# HPA_Module_V1p1.net
KiCad netlist of a schematic drawn in EAGLE
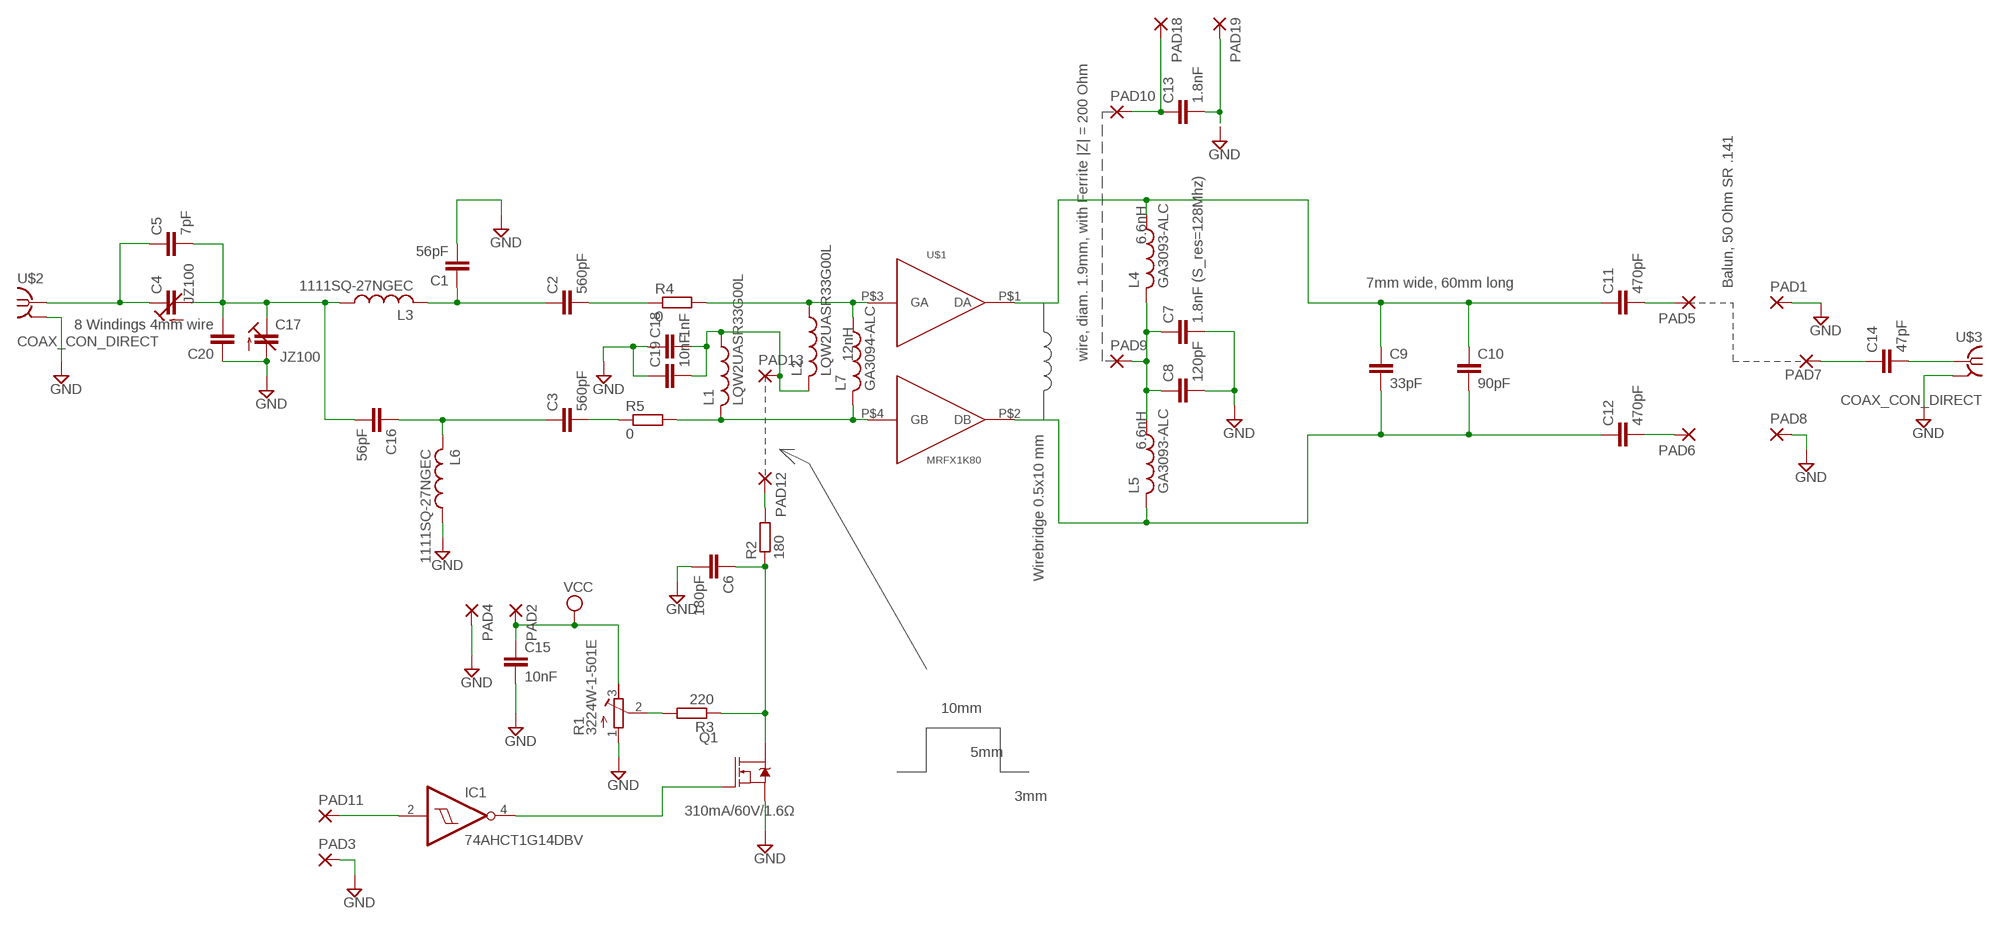
[diagram p0: schematic, sheet 1]

(export (version "E")
  (design (tool "Eeschema 10.0.6"))
  (components
    (comp (ref "C1")
      (value "56pF")
      (footprint "eagle-import:C1210")
      (libsource (lib "eagle-import") (part "C-EUC1210"))
    )
    (comp (ref "C2")
      (value "560pF")
      (footprint "eagle-import:C1210")
      (libsource (lib "eagle-import") (part "C-EUC1210"))
    )
    (comp (ref "C3")
      (value "560pF")
      (footprint "eagle-import:C1210")
      (libsource (lib "eagle-import") (part "C-EUC1210"))
    )
    (comp (ref "C4")
      (value "JZ100")
      (footprint "eagle-import:CTRIM3018_12")
      (libsource (lib "eagle-import") (part "C-TRIMM3018_12"))
    )
    (comp (ref "C5")
      (value "7pF")
      (footprint "eagle-import:C1210K")
      (libsource (lib "eagle-import") (part "C-EUC1210K"))
    )
    (comp (ref "C6")
      (value "180pF")
      (footprint "eagle-import:C0805")
      (libsource (lib "eagle-import") (part "C-EUC0805"))
    )
    (comp (ref "C7")
      (value "1.8nF (S_res=128Mhz)")
      (footprint "eagle-import:C1210")
      (libsource (lib "eagle-import") (part "C-EUC1210"))
    )
    (comp (ref "C8")
      (value "120pF")
      (footprint "eagle-import:C1210")
      (libsource (lib "eagle-import") (part "C-EUC1210"))
    )
    (comp (ref "C9")
      (value "33pF")
      (footprint "eagle-import:C2220K")
      (libsource (lib "eagle-import") (part "C-EUC2220K"))
    )
    (comp (ref "C10")
      (value "90pF")
      (footprint "eagle-import:C2220K")
      (libsource (lib "eagle-import") (part "C-EUC2220K"))
    )
    (comp (ref "C11")
      (value "470pF")
      (footprint "eagle-import:C1210")
      (libsource (lib "eagle-import") (part "C-EUC1210"))
    )
    (comp (ref "C12")
      (value "470pF")
      (footprint "eagle-import:C1210")
      (libsource (lib "eagle-import") (part "C-EUC1210"))
    )
    (comp (ref "C13")
      (value "1.8nF")
      (footprint "eagle-import:C1210")
      (libsource (lib "eagle-import") (part "C-EUC1210"))
    )
    (comp (ref "C14")
      (value "47pF")
      (footprint "eagle-import:C1210")
      (libsource (lib "eagle-import") (part "C-EUC1210"))
    )
    (comp (ref "C15")
      (value "10nF")
      (footprint "eagle-import:C0805")
      (libsource (lib "eagle-import") (part "C-EUC0805"))
    )
    (comp (ref "C16")
      (value "56pF")
      (footprint "eagle-import:C1210")
      (libsource (lib "eagle-import") (part "C-EUC1210"))
    )
    (comp (ref "C17")
      (value "JZ100")
      (footprint "eagle-import:CTRIM3018_12")
      (libsource (lib "eagle-import") (part "C-TRIMM3018_12"))
    )
    (comp (ref "C18")
      (value "1nF")
      (footprint "eagle-import:C0805")
      (libsource (lib "eagle-import") (part "C-EUC0805"))
    )
    (comp (ref "C19")
      (value "10nF")
      (footprint "eagle-import:C0805")
      (libsource (lib "eagle-import") (part "C-EUC0805"))
    )
    (comp (ref "C20")
      (value "8 Windings 4mm wire")
      (footprint "eagle-import:C1210K")
      (libsource (lib "eagle-import") (part "C-EUC1210K"))
    )
    (comp (ref "IC1")
      (value "74AHCT1G14DBV")
      (footprint "eagle-import:SOT23-5")
      (libsource (lib "eagle-import") (part "741G14DBVAHCT"))
    )
    (comp (ref "L1")
      (value "LQW2UASR33G00L")
      (footprint "eagle-import:L2825P")
      (libsource (lib "eagle-import") (part "L-USL2825P"))
    )
    (comp (ref "L2")
      (value "LQW2UASR33G00L")
      (footprint "eagle-import:L2825P")
      (libsource (lib "eagle-import") (part "L-USL2825P"))
    )
    (comp (ref "L3")
      (value "1111SQ-27NGEC")
      (footprint "eagle-import:L2825P")
      (libsource (lib "eagle-import") (part "L-USL2825P"))
    )
    (comp (ref "L4")
      (value "GA3093-ALC")
      (footprint "eagle-import:L4532P")
      (libsource (lib "eagle-import") (part "L-USL4532P"))
    )
    (comp (ref "L5")
      (value "GA3093-ALC")
      (footprint "eagle-import:L4532P")
      (libsource (lib "eagle-import") (part "L-USL4532P"))
    )
    (comp (ref "L6")
      (value "1111SQ-27NGEC")
      (footprint "eagle-import:L2825P")
      (libsource (lib "eagle-import") (part "L-USL2825P"))
    )
    (comp (ref "L7")
      (value "GA3094-ALC")
      (footprint "eagle-import:L4532P")
      (libsource (lib "eagle-import") (part "L-USL4532P"))
    )
    (comp (ref "PAD1")
      (value "SMD5")
      (footprint "eagle-import:SMD2,54-5,08")
      (libsource (lib "eagle-import") (part "SMD5"))
    )
    (comp (ref "PAD2")
      (value "SMD5")
      (footprint "eagle-import:SMD2,54-5,08")
      (libsource (lib "eagle-import") (part "SMD5"))
    )
    (comp (ref "PAD3")
      (value "SMD5")
      (footprint "eagle-import:SMD2,54-5,08")
      (libsource (lib "eagle-import") (part "SMD5"))
    )
    (comp (ref "PAD4")
      (value "SMD5")
      (footprint "eagle-import:SMD2,54-5,08")
      (libsource (lib "eagle-import") (part "SMD5"))
    )
    (comp (ref "PAD5")
      (value "SMD5")
      (footprint "eagle-import:SMD2,54-5,08")
      (libsource (lib "eagle-import") (part "SMD5"))
    )
    (comp (ref "PAD6")
      (value "SMD5")
      (footprint "eagle-import:SMD2,54-5,08")
      (libsource (lib "eagle-import") (part "SMD5"))
    )
    (comp (ref "PAD7")
      (value "SMD5")
      (footprint "eagle-import:SMD2,54-5,08")
      (libsource (lib "eagle-import") (part "SMD5"))
    )
    (comp (ref "PAD8")
      (value "SMD5")
      (footprint "eagle-import:SMD2,54-5,08")
      (libsource (lib "eagle-import") (part "SMD5"))
    )
    (comp (ref "PAD9")
      (value "SMD5")
      (footprint "eagle-import:SMD2,54-5,08")
      (libsource (lib "eagle-import") (part "SMD5"))
    )
    (comp (ref "PAD10")
      (value "SMD5")
      (footprint "eagle-import:SMD2,54-5,08")
      (libsource (lib "eagle-import") (part "SMD5"))
    )
    (comp (ref "PAD11")
      (value "SMD5")
      (footprint "eagle-import:SMD2,54-5,08")
      (libsource (lib "eagle-import") (part "SMD5"))
    )
    (comp (ref "PAD12")
      (value "SMD5")
      (footprint "eagle-import:SMD2,54-5,08")
      (libsource (lib "eagle-import") (part "SMD5"))
    )
    (comp (ref "PAD13")
      (value "SMD5")
      (footprint "eagle-import:SMD2,54-5,08")
      (libsource (lib "eagle-import") (part "SMD5"))
    )
    (comp (ref "PAD18")
      (value "SMD5")
      (footprint "eagle-import:SMD2,54-5,08")
      (libsource (lib "eagle-import") (part "SMD5"))
    )
    (comp (ref "PAD19")
      (value "SMD5")
      (footprint "eagle-import:SMD2,54-5,08")
      (libsource (lib "eagle-import") (part "SMD5"))
    )
    (comp (ref "Q1")
      (value "310mA/60V/1.6Ω")
      (footprint "eagle-import:SOT323")
      (libsource (lib "eagle-import") (part "MOSFET-NCH-2N7002PW"))
    )
    (comp (ref "R1")
      (value "3224W-1-501E")
      (footprint "eagle-import:RTRIM3224W")
      (libsource (lib "eagle-import") (part "R-TRIMM3224W"))
    )
    (comp (ref "R2")
      (value "180")
      (footprint "eagle-import:R0805")
      (libsource (lib "eagle-import") (part "R-EU_R0805"))
    )
    (comp (ref "R3")
      (value "220")
      (footprint "eagle-import:R0805")
      (libsource (lib "eagle-import") (part "R-EU_R0805"))
    )
    (comp (ref "R4")
      (value "0")
      (footprint "eagle-import:R1206")
      (libsource (lib "eagle-import") (part "R-EU_R1206"))
    )
    (comp (ref "R5")
      (value "0")
      (footprint "eagle-import:R1206")
      (libsource (lib "eagle-import") (part "R-EU_R1206"))
    )
    (comp (ref "U$1")
      (value "MRFX1K80")
      (footprint "eagle-import:NI-1230H-4S")
      (libsource (lib "eagle-import") (part "MRFX1K80"))
    )
    (comp (ref "U$2")
      (value "COAX_CON_DIRECT")
      (footprint "eagle-import:COAX.141")
      (libsource (lib "eagle-import") (part "COAX_CON_DIRECT"))
    )
    (comp (ref "U$3")
      (value "COAX_CON_DIRECT")
      (footprint "eagle-import:COAX.141")
      (libsource (lib "eagle-import") (part "COAX_CON_DIRECT"))
    )
  )
  (nets
    (net (code "1") (name "GND") (class "Default")
      (node (ref "C1") (pin "2") (pinfunction "2_2") (pintype "passive"))
      (node (ref "C13") (pin "2") (pinfunction "2_2") (pintype "passive"))
      (node (ref "C15") (pin "2") (pinfunction "2_2") (pintype "passive"))
      (node (ref "C17") (pin "-") (pinfunction "A_-") (pintype "passive"))
      (node (ref "C18") (pin "1") (pinfunction "1_1") (pintype "passive"))
      (node (ref "C19") (pin "1") (pinfunction "1_1") (pintype "passive"))
      (node (ref "C20") (pin "1") (pinfunction "1_1") (pintype "passive"))
      (node (ref "C6") (pin "2") (pinfunction "2_2") (pintype "passive"))
      (node (ref "C7") (pin "2") (pinfunction "2_2") (pintype "passive"))
      (node (ref "C8") (pin "2") (pinfunction "2_2") (pintype "passive"))
      (node (ref "L6") (pin "1") (pinfunction "1_1") (pintype "passive"))
      (node (ref "PAD1") (pin "1") (pinfunction "P_1") (pintype "passive"))
      (node (ref "PAD19") (pin "1") (pinfunction "P_1") (pintype "passive"))
      (node (ref "PAD3") (pin "1") (pinfunction "P_1") (pintype "passive"))
      (node (ref "PAD4") (pin "1") (pinfunction "P_1") (pintype "passive"))
      (node (ref "PAD8") (pin "1") (pinfunction "P_1") (pintype "passive"))
      (node (ref "Q1") (pin "2") (pinfunction "S_2") (pintype "bidirectional"))
      (node (ref "R1") (pin "1") (pinfunction "A_1") (pintype "passive"))
      (node (ref "U$2") (pin "P$2") (pinfunction "GND_P$2") (pintype "passive"))
      (node (ref "U$3") (pin "P$2") (pinfunction "GND_P$2") (pintype "passive"))
    )
    (net (code "2") (name "Net-(C1-Pad1)") (class "Default")
      (node (ref "C1") (pin "1") (pinfunction "1_1") (pintype "passive"))
      (node (ref "C2") (pin "1") (pinfunction "1_1") (pintype "passive"))
      (node (ref "L3") (pin "2") (pinfunction "2_2") (pintype "passive"))
    )
    (net (code "3") (name "Net-(C2-Pad2)") (class "Default")
      (node (ref "C2") (pin "2") (pinfunction "2_2") (pintype "passive"))
      (node (ref "R4") (pin "1") (pinfunction "1_1") (pintype "passive"))
    )
    (net (code "4") (name "Net-(C3-Pad2)") (class "Default")
      (node (ref "C3") (pin "2") (pinfunction "2_2") (pintype "passive"))
      (node (ref "R5") (pin "1") (pinfunction "1_1") (pintype "passive"))
    )
    (net (code "5") (name "Net-(C4-E)") (class "Default")
      (node (ref "C4") (pin "+") (pinfunction "E_+") (pintype "passive"))
      (node (ref "C5") (pin "1") (pinfunction "1_1") (pintype "passive"))
      (node (ref "U$2") (pin "P$1") (pinfunction "1_P$1") (pintype "passive"))
    )
    (net (code "6") (name "Net-(C16-Pad1)") (class "Default")
      (node (ref "C16") (pin "1") (pinfunction "1_1") (pintype "passive"))
      (node (ref "C3") (pin "1") (pinfunction "1_1") (pintype "passive"))
      (node (ref "L6") (pin "2") (pinfunction "2_2") (pintype "passive"))
    )
    (net (code "7") (name "Net-(C17-E)") (class "Default")
      (node (ref "C16") (pin "2") (pinfunction "2_2") (pintype "passive"))
      (node (ref "C17") (pin "+") (pinfunction "E_+") (pintype "passive"))
      (node (ref "C20") (pin "2") (pinfunction "2_2") (pintype "passive"))
      (node (ref "C4") (pin "-") (pinfunction "A_-") (pintype "passive"))
      (node (ref "C5") (pin "2") (pinfunction "2_2") (pintype "passive"))
      (node (ref "L3") (pin "1") (pinfunction "1_1") (pintype "passive"))
    )
    (net (code "8") (name "Net-(IC1A-I)") (class "Default")
      (node (ref "IC1") (pin "2") (pinfunction "I_2") (pintype "input"))
      (node (ref "PAD11") (pin "1") (pinfunction "P_1") (pintype "passive"))
    )
    (net (code "9") (name "Net-(IC1A-O)") (class "Default")
      (node (ref "IC1") (pin "4") (pinfunction "O_4") (pintype "output"))
      (node (ref "Q1") (pin "1") (pinfunction "G_1") (pintype "bidirectional"))
    )
    (net (code "10") (name "Net-(PAD5-P)") (class "Default")
      (node (ref "C11") (pin "2") (pinfunction "2_2") (pintype "passive"))
      (node (ref "PAD5") (pin "1") (pinfunction "P_1") (pintype "passive"))
    )
    (net (code "11") (name "Net-(PAD6-P)") (class "Default")
      (node (ref "C12") (pin "2") (pinfunction "2_2") (pintype "passive"))
      (node (ref "PAD6") (pin "1") (pinfunction "P_1") (pintype "passive"))
    )
    (net (code "12") (name "Net-(PAD7-P)") (class "Default")
      (node (ref "C14") (pin "1") (pinfunction "1_1") (pintype "passive"))
      (node (ref "PAD7") (pin "1") (pinfunction "P_1") (pintype "passive"))
    )
    (net (code "13") (name "Net-(PAD9-P)") (class "Default")
      (node (ref "C7") (pin "1") (pinfunction "1_1") (pintype "passive"))
      (node (ref "C8") (pin "1") (pinfunction "1_1") (pintype "passive"))
      (node (ref "L4") (pin "2") (pinfunction "2_2") (pintype "passive"))
      (node (ref "L5") (pin "1") (pinfunction "1_1") (pintype "passive"))
      (node (ref "PAD9") (pin "1") (pinfunction "P_1") (pintype "passive"))
    )
    (net (code "14") (name "Net-(PAD10-P)") (class "Default")
      (node (ref "C13") (pin "1") (pinfunction "1_1") (pintype "passive"))
      (node (ref "PAD10") (pin "1") (pinfunction "P_1") (pintype "passive"))
      (node (ref "PAD18") (pin "1") (pinfunction "P_1") (pintype "passive"))
    )
    (net (code "15") (name "Net-(PAD12-P)") (class "Default")
      (node (ref "PAD12") (pin "1") (pinfunction "P_1") (pintype "passive"))
      (node (ref "R2") (pin "2") (pinfunction "2_2") (pintype "passive"))
    )
    (net (code "16") (name "Net-(PAD13-P)") (class "Default")
      (node (ref "C18") (pin "2") (pinfunction "2_2") (pintype "passive"))
      (node (ref "C19") (pin "2") (pinfunction "2_2") (pintype "passive"))
      (node (ref "L1") (pin "1") (pinfunction "1_1") (pintype "passive"))
      (node (ref "L2") (pin "2") (pinfunction "2_2") (pintype "passive"))
      (node (ref "PAD13") (pin "1") (pinfunction "P_1") (pintype "passive"))
    )
    (net (code "17") (name "Net-(Q1-D)") (class "Default")
      (node (ref "C6") (pin "1") (pinfunction "1_1") (pintype "passive"))
      (node (ref "Q1") (pin "3") (pinfunction "D_3") (pintype "bidirectional"))
      (node (ref "R2") (pin "1") (pinfunction "1_1") (pintype "passive"))
      (node (ref "R3") (pin "1") (pinfunction "1_1") (pintype "passive"))
    )
    (net (code "18") (name "Net-(R1-S)") (class "Default")
      (node (ref "R1") (pin "2") (pinfunction "S_2") (pintype "passive"))
      (node (ref "R3") (pin "2") (pinfunction "2_2") (pintype "passive"))
    )
    (net (code "19") (name "Net-(U$1-DA)") (class "Default")
      (node (ref "C10") (pin "1") (pinfunction "1_1") (pintype "passive"))
      (node (ref "C11") (pin "1") (pinfunction "1_1") (pintype "passive"))
      (node (ref "C9") (pin "1") (pinfunction "1_1") (pintype "passive"))
      (node (ref "L4") (pin "1") (pinfunction "1_1") (pintype "passive"))
      (node (ref "U$1") (pin "P$1") (pinfunction "DA_P$1") (pintype "bidirectional"))
    )
    (net (code "20") (name "Net-(U$1-DB)") (class "Default")
      (node (ref "C10") (pin "2") (pinfunction "2_2") (pintype "passive"))
      (node (ref "C12") (pin "1") (pinfunction "1_1") (pintype "passive"))
      (node (ref "C9") (pin "2") (pinfunction "2_2") (pintype "passive"))
      (node (ref "L5") (pin "2") (pinfunction "2_2") (pintype "passive"))
      (node (ref "U$1") (pin "P$2") (pinfunction "DB_P$2") (pintype "bidirectional"))
    )
    (net (code "21") (name "Net-(U$1-GA)") (class "Default")
      (node (ref "L2") (pin "1") (pinfunction "1_1") (pintype "passive"))
      (node (ref "L7") (pin "1") (pinfunction "1_1") (pintype "passive"))
      (node (ref "R4") (pin "2") (pinfunction "2_2") (pintype "passive"))
      (node (ref "U$1") (pin "P$3") (pinfunction "GA_P$3") (pintype "bidirectional"))
    )
    (net (code "22") (name "Net-(U$1-GB)") (class "Default")
      (node (ref "L1") (pin "2") (pinfunction "2_2") (pintype "passive"))
      (node (ref "L7") (pin "2") (pinfunction "2_2") (pintype "passive"))
      (node (ref "R5") (pin "2") (pinfunction "2_2") (pintype "passive"))
      (node (ref "U$1") (pin "P$4") (pinfunction "GB_P$4") (pintype "bidirectional"))
    )
    (net (code "23") (name "Net-(U$3-1)") (class "Default")
      (node (ref "C14") (pin "2") (pinfunction "2_2") (pintype "passive"))
      (node (ref "U$3") (pin "P$1") (pinfunction "1_P$1") (pintype "passive"))
    )
    (net (code "24") (name "VCC") (class "Default")
      (node (ref "C15") (pin "1") (pinfunction "1_1") (pintype "passive"))
      (node (ref "PAD2") (pin "1") (pinfunction "P_1") (pintype "passive"))
      (node (ref "R1") (pin "3") (pinfunction "E_3") (pintype "passive"))
    )
  )
)
